# Propulsion_v2.net
KiCad netlist of a schematic drawn in Altium Designer
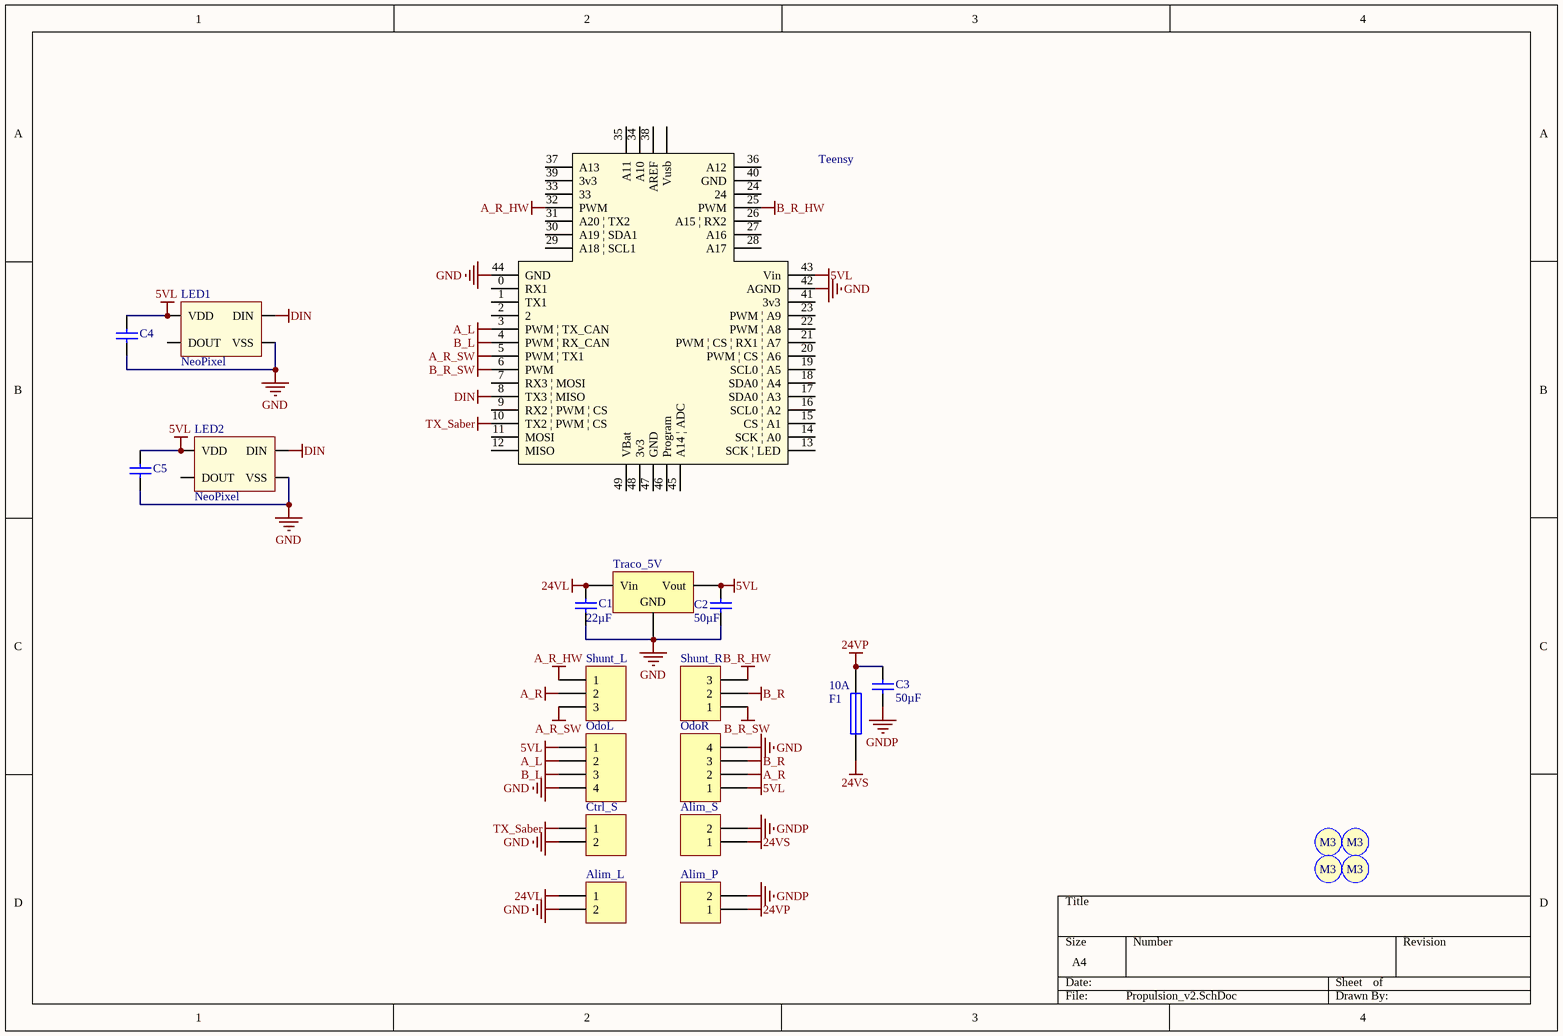
[diagram p0: Propulsion_v2.SchDoc]

(export (version "E")
  (design (tool "Eeschema 10.0.6"))
  (components
    (comp (ref "Alim_L")
      (value "Minifit Jr 2x1H")
      (footprint "Molex_MiniFitJr_2x1H")
      (description "Molex Minifit Jr 2x1H")
      (fields (field (name "PUBLISHER") "Altium Limited"))
      (libsource (lib "Miscellaneous Connectors") (part "Header 2"))
    )
    (comp (ref "Alim_P")
      (value "Minifit Jr 2x1H")
      (footprint "Molex_MiniFitJr_2x1H")
      (description "Molex Minifit Jr 2x1H")
      (fields (field (name "PUBLISHER") "Altium Limited"))
      (libsource (lib "") (part "Header 2_1"))
    )
    (comp (ref "Alim_S")
      (value "Minifit Jr 2x1H")
      (footprint "robot:Molex_MiniFitJr_2x1H")
      (description "Molex Minifit Jr 2x1H")
      (fields (field (name "PUBLISHER") "Altium Limited"))
      (libsource (lib "") (part "Header 2_1"))
    )
    (comp (ref "C1")
      (value "22µF")
      (footprint "3.2X1.6X1.1")
      (description "Capacitor")
      (fields (field (name "Comment") "Cap22uF") (field (name "PUBLISHER") "Altium Limited"))
      (libsource (lib "Miscellaneous Devices") (part "Cap"))
    )
    (comp (ref "C2")
      (value "50µF")
      (footprint "3.2X1.6X1.1")
      (description "Capacitor")
      (fields (field (name "Comment") "Cap50uF") (field (name "PUBLISHER") "Altium Limited"))
      (libsource (lib "Miscellaneous Devices") (part "Cap"))
    )
    (comp (ref "C3")
      (value "50µF")
      (footprint "robot:Condensateur")
      (description "Capacitor")
      (fields (field (name "Comment") "Cap50uF") (field (name "PUBLISHER") "Altium Limited"))
      (libsource (lib "Miscellaneous Devices") (part "Cap"))
    )
    (comp (ref "C4")
      (value "Cap")
      (footprint "3.2X1.6X1.1")
      (description "Capacitor")
      (fields (field (name "PUBLISHER") "Altium Limited"))
      (libsource (lib "Miscellaneous Devices") (part "Cap"))
    )
    (comp (ref "C5")
      (value "Cap")
      (footprint "3.2X1.6X1.1")
      (description "Capacitor")
      (fields (field (name "PUBLISHER") "Altium Limited"))
      (libsource (lib "Miscellaneous Devices") (part "Cap"))
    )
    (comp (ref "Ctrl_S")
      (value "SPOX 2x1H")
      (footprint "robot:Molex SPOX 2x1H")
      (description "Molex SPOX Jr 2x1H")
      (fields (field (name "PUBLISHER") "Altium Limited"))
      (libsource (lib "Miscellaneous Connectors") (part "Header 2"))
    )
    (comp (ref "F1")
      (value "10A")
      (footprint "robot:Fuse")
      (description "Fuse")
      (fields (field (name "PUBLISHER") "Altium Limited"))
      (libsource (lib "Miscellaneous Devices") (part "Fuse 1"))
    )
    (comp (ref "LED1")
      (value "NeoPixel")
      (footprint "robot:Neopixel")
      (libsource (lib "robot") (part "NeoPixel"))
    )
    (comp (ref "LED2")
      (value "NeoPixel")
      (footprint "robot:Neopixel")
      (libsource (lib "robot") (part "NeoPixel"))
    )
    (comp (ref "OdoL")
      (value "SPOX 4x1H")
      (footprint "robot:Molex SPOX 4x1H")
      (description "Molex SPOX 4x1H")
      (fields (field (name "PUBLISHER") "Altium Limited"))
      (libsource (lib "") (part "Header 4H_1"))
    )
    (comp (ref "OdoR")
      (value "SPOX 4x1H")
      (footprint "robot:Molex SPOX 4x1H")
      (description "Molex SPOX 4x1H")
      (fields (field (name "PUBLISHER") "Altium Limited"))
      (libsource (lib "Miscellaneous Connectors") (part "Header 4H"))
    )
    (comp (ref "S1")
      (value "Screw M3")
      (footprint "robot:Screw M3")
      (libsource (lib "robot") (part "Screw M3"))
    )
    (comp (ref "S2")
      (value "Screw M3")
      (footprint "robot:Screw M3")
      (libsource (lib "robot") (part "Screw M3"))
    )
    (comp (ref "S3")
      (value "Screw M3")
      (footprint "robot:Screw M3")
      (libsource (lib "robot") (part "Screw M3"))
    )
    (comp (ref "S4")
      (value "Screw M3")
      (footprint "robot:Screw M3")
      (libsource (lib "robot") (part "Screw M3"))
    )
    (comp (ref "Shunt_L")
      (value "Shunt selector")
      (footprint "HDR1X3")
      (description "Header, 3-Pin")
      (fields (field (name "PUBLISHER") "Altium Limited"))
      (libsource (lib "") (part "Header 3_1"))
    )
    (comp (ref "Shunt_R")
      (value "Shunt selector")
      (footprint "HDR1X3")
      (description "Header, 3-Pin")
      (fields (field (name "PUBLISHER") "Altium Limited"))
      (libsource (lib "Miscellaneous Connectors") (part "Header 3"))
    )
    (comp (ref "Teensy")
      (value "Teensy 3.2")
      (footprint "robot:teensy")
      (libsource (lib "robot") (part "teensy3.2"))
    )
    (comp (ref "Traco_5V")
      (value "Traco TRS2-2450")
      (footprint "robot:TRS0.5")
      (description "Voltage Regulator")
      (fields (field (name "PUBLISHER") "Altium Limited"))
      (libsource (lib "Miscellaneous Devices") (part "Volt Reg"))
    )
  )
  (nets
    (net (code "1") (name "5VL") (class "Default")
      (node (ref "C2") (pin "1") (pinfunction "1_1") (pintype "passive"))
      (node (ref "C4") (pin "2") (pinfunction "2_2") (pintype "passive"))
      (node (ref "C5") (pin "2") (pinfunction "2_2") (pintype "passive"))
      (node (ref "LED1") (pin "3") (pinfunction "VDD_3") (pintype "passive"))
      (node (ref "LED2") (pin "3") (pinfunction "VDD_3") (pintype "passive"))
      (node (ref "OdoL") (pin "1") (pinfunction "1_1") (pintype "passive"))
      (node (ref "OdoR") (pin "1") (pinfunction "1_1") (pintype "passive"))
      (node (ref "Teensy") (pin "43") (pinfunction "Vin_43") (pintype "passive"))
      (node (ref "Traco_5V") (pin "3") (pinfunction "Vout_3") (pintype "passive"))
    )
    (net (code "2") (name "24VL") (class "Default")
      (node (ref "Alim_L") (pin "1") (pinfunction "1_1") (pintype "passive"))
      (node (ref "C1") (pin "2") (pinfunction "2_2") (pintype "passive"))
      (node (ref "Traco_5V") (pin "1") (pinfunction "Vin_1") (pintype "passive"))
    )
    (net (code "3") (name "24VP") (class "Default")
      (node (ref "Alim_P") (pin "1") (pinfunction "1_1") (pintype "passive"))
      (node (ref "C3") (pin "1") (pinfunction "1_1") (pintype "passive"))
      (node (ref "F1") (pin "2") (pinfunction "2_2") (pintype "passive"))
    )
    (net (code "4") (name "24VS") (class "Default")
      (node (ref "Alim_S") (pin "1") (pinfunction "1_1") (pintype "passive"))
      (node (ref "F1") (pin "1") (pinfunction "1_1") (pintype "passive"))
    )
    (net (code "5") (name "A_L") (class "Default")
      (node (ref "OdoL") (pin "2") (pinfunction "2_2") (pintype "passive"))
      (node (ref "Teensy") (pin "3") (pinfunction "PWM_¦_TX_CAN_3") (pintype "passive"))
    )
    (net (code "6") (name "A_R") (class "Default")
      (node (ref "OdoR") (pin "2") (pinfunction "2_2") (pintype "passive"))
      (node (ref "Shunt_L") (pin "2") (pinfunction "2_2") (pintype "passive"))
    )
    (net (code "7") (name "A_R_HW") (class "Default")
      (node (ref "Shunt_L") (pin "1") (pinfunction "1_1") (pintype "passive"))
      (node (ref "Teensy") (pin "32") (pinfunction "PWM_32") (pintype "passive"))
    )
    (net (code "8") (name "A_R_SW") (class "Default")
      (node (ref "Shunt_L") (pin "3") (pinfunction "3_3") (pintype "passive"))
      (node (ref "Teensy") (pin "5") (pinfunction "PWM_¦_TX1_5") (pintype "passive"))
    )
    (net (code "9") (name "B_L") (class "Default")
      (node (ref "OdoL") (pin "3") (pinfunction "3_3") (pintype "passive"))
      (node (ref "Teensy") (pin "4") (pinfunction "PWM_¦_RX_CAN_4") (pintype "passive"))
    )
    (net (code "10") (name "B_R") (class "Default")
      (node (ref "OdoR") (pin "3") (pinfunction "3_3") (pintype "passive"))
      (node (ref "Shunt_R") (pin "2") (pinfunction "2_2") (pintype "passive"))
    )
    (net (code "11") (name "B_R_HW") (class "Default")
      (node (ref "Shunt_R") (pin "3") (pinfunction "3_3") (pintype "passive"))
      (node (ref "Teensy") (pin "25") (pinfunction "PWM_25") (pintype "passive"))
    )
    (net (code "12") (name "B_R_SW") (class "Default")
      (node (ref "Shunt_R") (pin "1") (pinfunction "1_1") (pintype "passive"))
      (node (ref "Teensy") (pin "6") (pinfunction "PWM_6") (pintype "passive"))
    )
    (net (code "13") (name "DIN") (class "Default")
      (node (ref "LED1") (pin "2") (pinfunction "DIN_2") (pintype "passive"))
      (node (ref "LED2") (pin "2") (pinfunction "DIN_2") (pintype "passive"))
      (node (ref "Teensy") (pin "8") (pinfunction "TX3_¦_MISO_8") (pintype "passive"))
    )
    (net (code "14") (name "GND") (class "Default")
      (node (ref "Alim_L") (pin "2") (pinfunction "2_2") (pintype "passive"))
      (node (ref "C1") (pin "1") (pinfunction "1_1") (pintype "passive"))
      (node (ref "C2") (pin "2") (pinfunction "2_2") (pintype "passive"))
      (node (ref "C4") (pin "1") (pinfunction "1_1") (pintype "passive"))
      (node (ref "C5") (pin "1") (pinfunction "1_1") (pintype "passive"))
      (node (ref "Ctrl_S") (pin "2") (pinfunction "2_2") (pintype "passive"))
      (node (ref "LED1") (pin "1") (pinfunction "VSS_1") (pintype "passive"))
      (node (ref "LED2") (pin "1") (pinfunction "VSS_1") (pintype "passive"))
      (node (ref "OdoL") (pin "4") (pinfunction "4_4") (pintype "passive"))
      (node (ref "OdoR") (pin "4") (pinfunction "4_4") (pintype "passive"))
      (node (ref "Teensy") (pin "42") (pinfunction "AGND_42") (pintype "passive"))
      (node (ref "Teensy") (pin "44") (pinfunction "GND_44") (pintype "passive"))
      (node (ref "Traco_5V") (pin "2") (pinfunction "GND_2") (pintype "passive"))
    )
    (net (code "15") (name "GNDP") (class "Default")
      (node (ref "Alim_P") (pin "2") (pinfunction "2_2") (pintype "passive"))
      (node (ref "Alim_S") (pin "2") (pinfunction "2_2") (pintype "passive"))
      (node (ref "C3") (pin "2") (pinfunction "2_2") (pintype "passive"))
    )
    (net (code "16") (name "TX_Saber") (class "Default")
      (node (ref "Ctrl_S") (pin "1") (pinfunction "1_1") (pintype "passive"))
      (node (ref "Teensy") (pin "10") (pinfunction "TX2_¦_PWM_¦_CS_10") (pintype "passive"))
    )
    (net (code "17") (name "unconnected-(LED1-DOUT-Pad4)") (class "Default")
      (node (ref "LED1") (pin "4") (pinfunction "DOUT_4") (pintype "passive"))
    )
    (net (code "18") (name "unconnected-(LED2-DOUT-Pad4)") (class "Default")
      (node (ref "LED2") (pin "4") (pinfunction "DOUT_4") (pintype "passive"))
    )
    (net (code "19") (name "unconnected-(Teensy-3v3-Pad39)") (class "Default")
      (node (ref "Teensy") (pin "39") (pinfunction "3v3_39") (pintype "passive"))
    )
    (net (code "20") (name "unconnected-(Teensy-3v3-Pad41)") (class "Default")
      (node (ref "Teensy") (pin "41") (pinfunction "3v3_41") (pintype "passive"))
    )
    (net (code "21") (name "unconnected-(Teensy-3v3-Pad48)") (class "Default")
      (node (ref "Teensy") (pin "48") (pinfunction "3v3_48") (pintype "passive"))
    )
    (net (code "22") (name "unconnected-(Teensy-A10-Pad34)") (class "Default")
      (node (ref "Teensy") (pin "34") (pinfunction "A10_34") (pintype "passive"))
    )
    (net (code "23") (name "unconnected-(Teensy-A11-Pad35)") (class "Default")
      (node (ref "Teensy") (pin "35") (pinfunction "A11_35") (pintype "passive"))
    )
    (net (code "24") (name "unconnected-(Teensy-A12-Pad36)") (class "Default")
      (node (ref "Teensy") (pin "36") (pinfunction "A12_36") (pintype "passive"))
    )
    (net (code "25") (name "unconnected-(Teensy-A13-Pad37)") (class "Default")
      (node (ref "Teensy") (pin "37") (pinfunction "A13_37") (pintype "passive"))
    )
    (net (code "26") (name "unconnected-(Teensy-A14_¦_ADC-Pad45)") (class "Default")
      (node (ref "Teensy") (pin "45") (pinfunction "A14_¦_ADC_45") (pintype "passive"))
    )
    (net (code "27") (name "unconnected-(Teensy-A15_¦_RX2-Pad26)") (class "Default")
      (node (ref "Teensy") (pin "26") (pinfunction "A15_¦_RX2_26") (pintype "passive"))
    )
    (net (code "28") (name "unconnected-(Teensy-A16-Pad27)") (class "Default")
      (node (ref "Teensy") (pin "27") (pinfunction "A16_27") (pintype "passive"))
    )
    (net (code "29") (name "unconnected-(Teensy-A17-Pad28)") (class "Default")
      (node (ref "Teensy") (pin "28") (pinfunction "A17_28") (pintype "passive"))
    )
    (net (code "30") (name "unconnected-(Teensy-A18_¦_SCL1-Pad29)") (class "Default")
      (node (ref "Teensy") (pin "29") (pinfunction "A18_¦_SCL1_29") (pintype "passive"))
    )
    (net (code "31") (name "unconnected-(Teensy-A19_¦_SDA1-Pad30)") (class "Default")
      (node (ref "Teensy") (pin "30") (pinfunction "A19_¦_SDA1_30") (pintype "passive"))
    )
    (net (code "32") (name "unconnected-(Teensy-A20_¦_TX2-Pad31)") (class "Default")
      (node (ref "Teensy") (pin "31") (pinfunction "A20_¦_TX2_31") (pintype "passive"))
    )
    (net (code "33") (name "unconnected-(Teensy-AREF-Pad38)") (class "Default")
      (node (ref "Teensy") (pin "38") (pinfunction "AREF_38") (pintype "passive"))
    )
    (net (code "34") (name "unconnected-(Teensy-CS_¦_A1-Pad15)") (class "Default")
      (node (ref "Teensy") (pin "15") (pinfunction "CS_¦_A1_15") (pintype "passive"))
    )
    (net (code "35") (name "unconnected-(Teensy-GND-Pad40)") (class "Default")
      (node (ref "Teensy") (pin "40") (pinfunction "GND_40") (pintype "passive"))
    )
    (net (code "36") (name "unconnected-(Teensy-GND-Pad47)") (class "Default")
      (node (ref "Teensy") (pin "47") (pinfunction "GND_47") (pintype "passive"))
    )
    (net (code "37") (name "unconnected-(Teensy-MISO-Pad12)") (class "Default")
      (node (ref "Teensy") (pin "12") (pinfunction "MISO_12") (pintype "passive"))
    )
    (net (code "38") (name "unconnected-(Teensy-MOSI-Pad11)") (class "Default")
      (node (ref "Teensy") (pin "11") (pinfunction "MOSI_11") (pintype "passive"))
    )
    (net (code "39") (name "unconnected-(Teensy-PWM_¦_A8-Pad22)") (class "Default")
      (node (ref "Teensy") (pin "22") (pinfunction "PWM_¦_A8_22") (pintype "passive"))
    )
    (net (code "40") (name "unconnected-(Teensy-PWM_¦_A9-Pad23)") (class "Default")
      (node (ref "Teensy") (pin "23") (pinfunction "PWM_¦_A9_23") (pintype "passive"))
    )
    (net (code "41") (name "unconnected-(Teensy-PWM_¦_CS_¦_A6-Pad20)") (class "Default")
      (node (ref "Teensy") (pin "20") (pinfunction "PWM_¦_CS_¦_A6_20") (pintype "passive"))
    )
    (net (code "42") (name "unconnected-(Teensy-PWM_¦_CS_¦_RX1_¦_A7-Pad21)") (class "Default")
      (node (ref "Teensy") (pin "21") (pinfunction "PWM_¦_CS_¦_RX1_¦_A7_21") (pintype "passive"))
    )
    (net (code "43") (name "unconnected-(Teensy-Pad2)") (class "Default")
      (node (ref "Teensy") (pin "2") (pinfunction "2_2") (pintype "passive"))
    )
    (net (code "44") (name "unconnected-(Teensy-Pad24)") (class "Default")
      (node (ref "Teensy") (pin "24") (pinfunction "24_24") (pintype "passive"))
    )
    (net (code "45") (name "unconnected-(Teensy-Pad33)") (class "Default")
      (node (ref "Teensy") (pin "33") (pinfunction "33_33") (pintype "passive"))
    )
    (net (code "46") (name "unconnected-(Teensy-Program-Pad46)") (class "Default")
      (node (ref "Teensy") (pin "46") (pinfunction "Program_46") (pintype "passive"))
    )
    (net (code "47") (name "unconnected-(Teensy-RX1-Pad0)") (class "Default")
      (node (ref "Teensy") (pin "0") (pinfunction "RX1_0") (pintype "passive"))
    )
    (net (code "48") (name "unconnected-(Teensy-RX2_¦_PWM_¦_CS-Pad9)") (class "Default")
      (node (ref "Teensy") (pin "9") (pinfunction "RX2_¦_PWM_¦_CS_9") (pintype "passive"))
    )
    (net (code "49") (name "unconnected-(Teensy-RX3_¦_MOSI-Pad7)") (class "Default")
      (node (ref "Teensy") (pin "7") (pinfunction "RX3_¦_MOSI_7") (pintype "passive"))
    )
    (net (code "50") (name "unconnected-(Teensy-SCK_¦_A0-Pad14)") (class "Default")
      (node (ref "Teensy") (pin "14") (pinfunction "SCK_¦_A0_14") (pintype "passive"))
    )
    (net (code "51") (name "unconnected-(Teensy-SCK_¦_LED-Pad13)") (class "Default")
      (node (ref "Teensy") (pin "13") (pinfunction "SCK_¦_LED_13") (pintype "passive"))
    )
    (net (code "52") (name "unconnected-(Teensy-SCL0_¦_A2-Pad16)") (class "Default")
      (node (ref "Teensy") (pin "16") (pinfunction "SCL0_¦_A2_16") (pintype "passive"))
    )
    (net (code "53") (name "unconnected-(Teensy-SCL0_¦_A5-Pad19)") (class "Default")
      (node (ref "Teensy") (pin "19") (pinfunction "SCL0_¦_A5_19") (pintype "passive"))
    )
    (net (code "54") (name "unconnected-(Teensy-SDA0_¦_A3-Pad17)") (class "Default")
      (node (ref "Teensy") (pin "17") (pinfunction "SDA0_¦_A3_17") (pintype "passive"))
    )
    (net (code "55") (name "unconnected-(Teensy-SDA0_¦_A4-Pad18)") (class "Default")
      (node (ref "Teensy") (pin "18") (pinfunction "SDA0_¦_A4_18") (pintype "passive"))
    )
    (net (code "56") (name "unconnected-(Teensy-TX1-Pad1)") (class "Default")
      (node (ref "Teensy") (pin "1") (pinfunction "TX1_1") (pintype "passive"))
    )
    (net (code "57") (name "unconnected-(Teensy-VBat-Pad49)") (class "Default")
      (node (ref "Teensy") (pin "49") (pinfunction "VBat_49") (pintype "passive"))
    )
    (net (code "58") (name "unconnected-(Teensy-Vusb-Pad50)") (class "Default")
      (node (ref "Teensy") (pin "50") (pinfunction "Vusb_50") (pintype "passive"))
    )
  )
)
